# IOMOD-MCP23008-v1_0.net
KiCad netlist of a schematic drawn in EAGLE
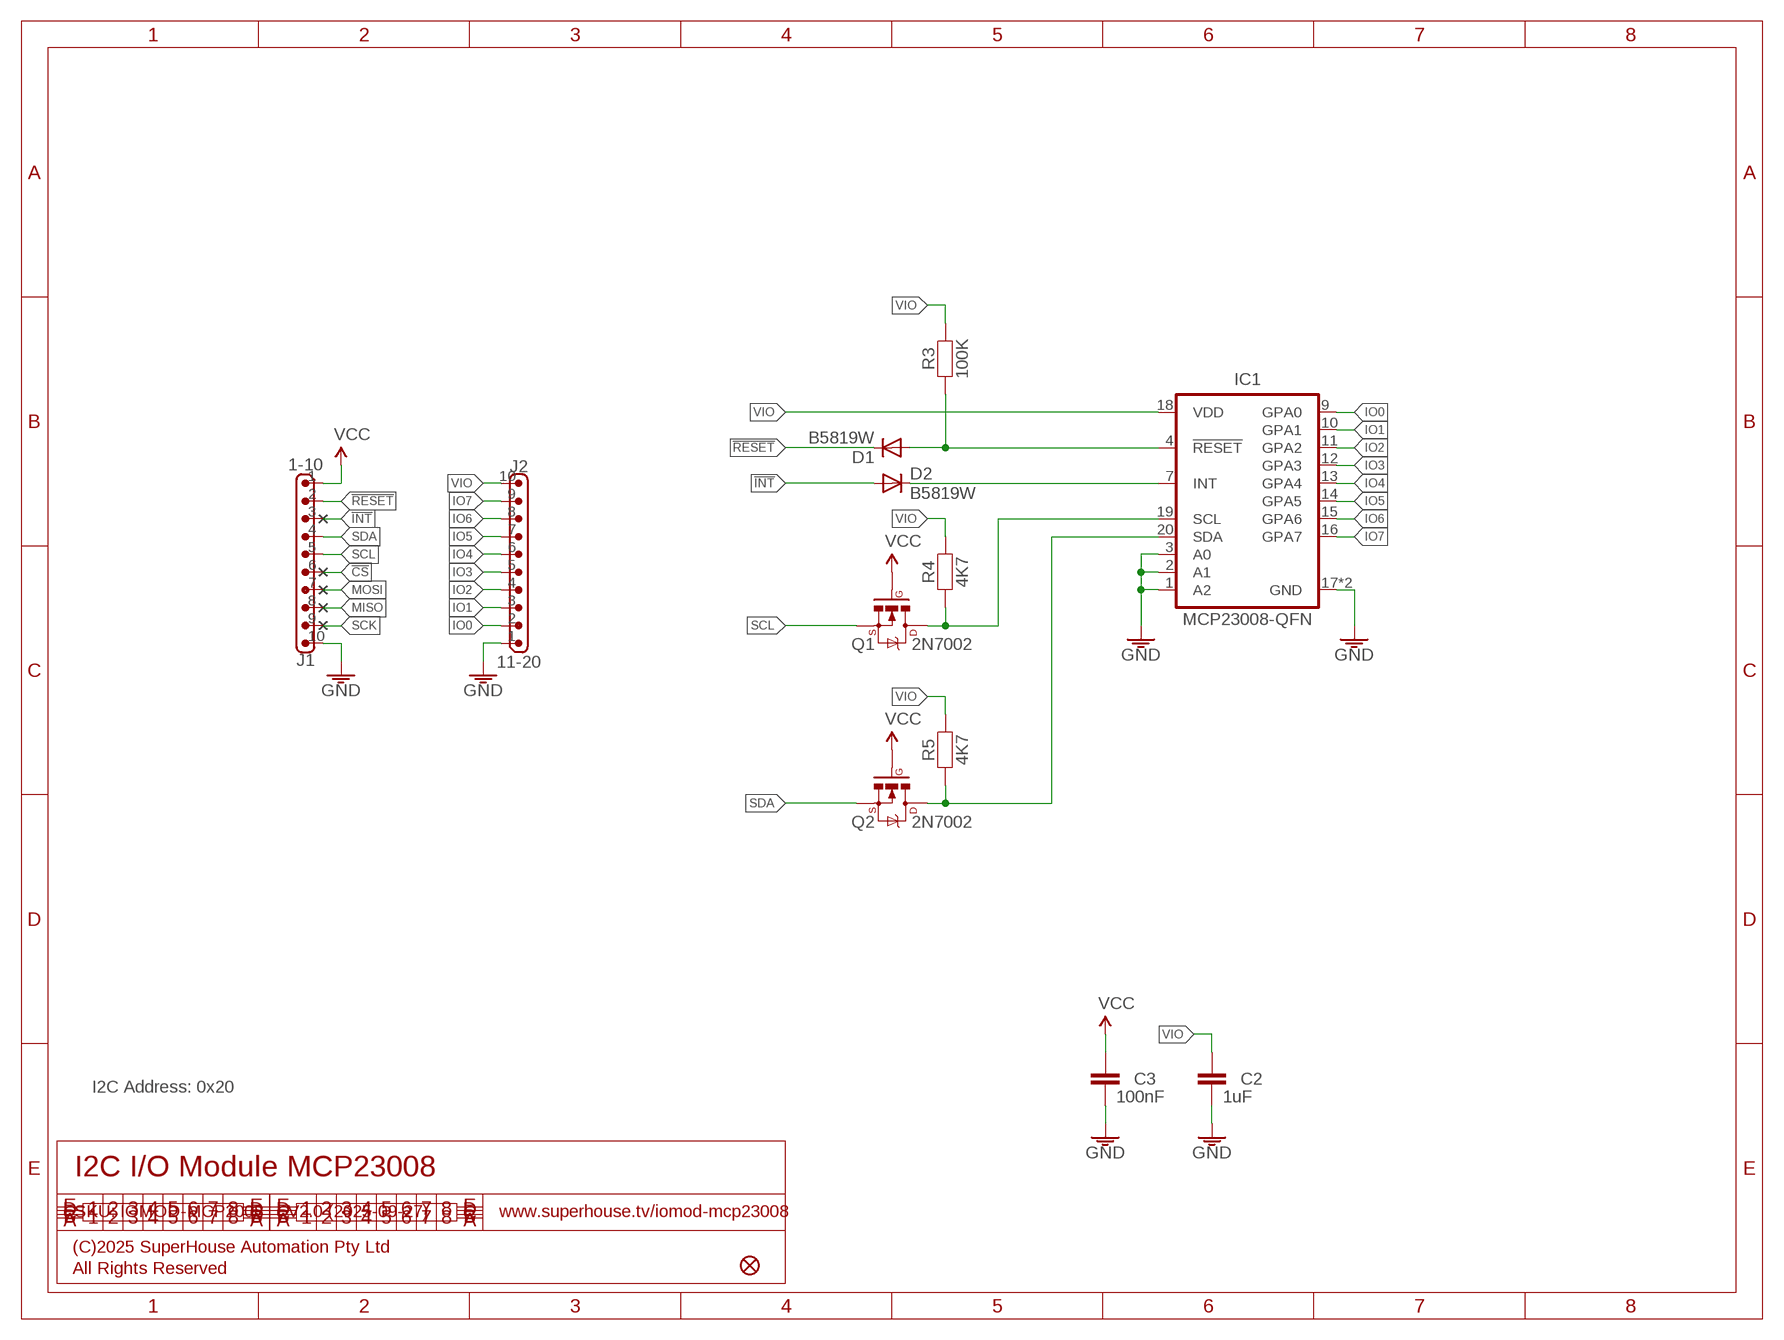
[diagram p0: schematic, sheet 1]

(export (version "E")
  (design (tool "Eeschema 10.0.6"))
  (components
    (comp (ref "C2")
      (value "1uF")
      (footprint "eagle-import:C0603")
      (libsource (lib "eagle-import") (part "CAP0603"))
    )
    (comp (ref "C3")
      (value "100nF")
      (footprint "eagle-import:C0603")
      (libsource (lib "eagle-import") (part "CAP0603"))
    )
    (comp (ref "D1")
      (value "B5819W")
      (footprint "eagle-import:SOD-123")
      (libsource (lib "eagle-import") (part "DIODE-SOD123"))
    )
    (comp (ref "D2")
      (value "B5819W")
      (footprint "eagle-import:SOD-123")
      (libsource (lib "eagle-import") (part "DIODE-SOD123"))
    )
    (comp (ref "FID1")
      (value "FIDUCIAL1X2")
      (footprint "eagle-import:FIDUCIAL-1X2")
      (libsource (lib "eagle-import") (part "FIDUCIAL1X2"))
    )
    (comp (ref "IC1")
      (value "MCP23008-QFN")
      (footprint "eagle-import:QFN-20")
      (libsource (lib "eagle-import") (part "MCP23008-QFN"))
    )
    (comp (ref "J1")
      (value "1-10")
      (footprint "eagle-import:1X10-2.00-P-ABOVE")
      (libsource (lib "eagle-import") (part "M10-2.00-P-ABOVE"))
    )
    (comp (ref "J2")
      (value "11-20")
      (footprint "eagle-import:1X10-2.00-P-ABOVE")
      (libsource (lib "eagle-import") (part "M10-2.00-P-ABOVE"))
    )
    (comp (ref "Q1")
      (value "2N7002")
      (footprint "eagle-import:SOT23-3")
      (libsource (lib "eagle-import") (part "MOSFET-NCHANNEL-233"))
    )
    (comp (ref "Q2")
      (value "2N7002")
      (footprint "eagle-import:SOT23-3")
      (libsource (lib "eagle-import") (part "MOSFET-NCHANNEL-233"))
    )
    (comp (ref "R3")
      (value "100K")
      (footprint "eagle-import:R0603")
      (libsource (lib "eagle-import") (part "RESISTOR0603"))
    )
    (comp (ref "R4")
      (value "4K7")
      (footprint "eagle-import:R0603")
      (libsource (lib "eagle-import") (part "RESISTOR0603"))
    )
    (comp (ref "R5")
      (value "4K7")
      (footprint "eagle-import:R0603")
      (libsource (lib "eagle-import") (part "RESISTOR0603"))
    )
  )
  (nets
    (net (code "1") (name "/~{CS}") (class "Default")
      (node (ref "J1") (pin "6") (pinfunction "6_6") (pintype "passive"))
    )
    (net (code "2") (name "/~{INT}") (class "Default")
      (node (ref "D2") (pin "2") (pinfunction "A_2") (pintype "passive"))
      (node (ref "J1") (pin "3") (pinfunction "3_3") (pintype "passive"))
    )
    (net (code "3") (name "/~{RESET}") (class "Default")
      (node (ref "D1") (pin "1") (pinfunction "C_1") (pintype "passive"))
      (node (ref "J1") (pin "2") (pinfunction "2_2") (pintype "passive"))
    )
    (net (code "4") (name "GND") (class "Default")
      (node (ref "C2") (pin "2") (pinfunction "2_2") (pintype "passive"))
      (node (ref "C3") (pin "2") (pinfunction "2_2") (pintype "passive"))
      (node (ref "IC1") (pin "1") (pinfunction "A2_1") (pintype "input"))
      (node (ref "IC1") (pin "17") (pinfunction "GND_17") (pintype "power_in"))
      (node (ref "IC1") (pin "2") (pinfunction "A1_2") (pintype "input"))
      (node (ref "IC1") (pin "3") (pinfunction "A0_3") (pintype "input"))
      (node (ref "IC1") (pin "TGND") (pinfunction "GND_TGND") (pintype "power_in"))
      (node (ref "J1") (pin "10") (pinfunction "10_10") (pintype "passive"))
      (node (ref "J2") (pin "1") (pinfunction "1_1") (pintype "passive"))
    )
    (net (code "5") (name "IO0") (class "Default")
      (node (ref "IC1") (pin "9") (pinfunction "GPA0_9") (pintype "bidirectional"))
      (node (ref "J2") (pin "2") (pinfunction "2_2") (pintype "passive"))
    )
    (net (code "6") (name "IO1") (class "Default")
      (node (ref "IC1") (pin "10") (pinfunction "GPA1_10") (pintype "bidirectional"))
      (node (ref "J2") (pin "3") (pinfunction "3_3") (pintype "passive"))
    )
    (net (code "7") (name "IO2") (class "Default")
      (node (ref "IC1") (pin "11") (pinfunction "GPA2_11") (pintype "bidirectional"))
      (node (ref "J2") (pin "4") (pinfunction "4_4") (pintype "passive"))
    )
    (net (code "8") (name "IO3") (class "Default")
      (node (ref "IC1") (pin "12") (pinfunction "GPA3_12") (pintype "bidirectional"))
      (node (ref "J2") (pin "5") (pinfunction "5_5") (pintype "passive"))
    )
    (net (code "9") (name "IO4") (class "Default")
      (node (ref "IC1") (pin "13") (pinfunction "GPA4_13") (pintype "bidirectional"))
      (node (ref "J2") (pin "6") (pinfunction "6_6") (pintype "passive"))
    )
    (net (code "10") (name "IO5") (class "Default")
      (node (ref "IC1") (pin "14") (pinfunction "GPA5_14") (pintype "bidirectional"))
      (node (ref "J2") (pin "7") (pinfunction "7_7") (pintype "passive"))
    )
    (net (code "11") (name "IO6") (class "Default")
      (node (ref "IC1") (pin "15") (pinfunction "GPA6_15") (pintype "bidirectional"))
      (node (ref "J2") (pin "8") (pinfunction "8_8") (pintype "passive"))
    )
    (net (code "12") (name "IO7") (class "Default")
      (node (ref "IC1") (pin "16") (pinfunction "GPA7_16") (pintype "bidirectional"))
      (node (ref "J2") (pin "9") (pinfunction "9_9") (pintype "passive"))
    )
    (net (code "13") (name "MISO") (class "Default")
      (node (ref "J1") (pin "8") (pinfunction "8_8") (pintype "passive"))
    )
    (net (code "14") (name "MOSI") (class "Default")
      (node (ref "J1") (pin "7") (pinfunction "7_7") (pintype "passive"))
    )
    (net (code "15") (name "Net-(D1-A)") (class "Default")
      (node (ref "D1") (pin "2") (pinfunction "A_2") (pintype "passive"))
      (node (ref "IC1") (pin "4") (pinfunction "~{RESET}_4") (pintype "input"))
      (node (ref "R3") (pin "1") (pinfunction "1_1") (pintype "passive"))
    )
    (net (code "16") (name "Net-(D2-C)") (class "Default")
      (node (ref "D2") (pin "1") (pinfunction "C_1") (pintype "passive"))
      (node (ref "IC1") (pin "7") (pinfunction "INT_7") (pintype "output"))
    )
    (net (code "17") (name "Net-(IC1-SCL)") (class "Default")
      (node (ref "IC1") (pin "19") (pinfunction "SCL_19") (pintype "input"))
      (node (ref "Q1") (pin "3") (pinfunction "D_3") (pintype "passive"))
      (node (ref "R4") (pin "1") (pinfunction "1_1") (pintype "passive"))
    )
    (net (code "18") (name "Net-(IC1-SDA)") (class "Default")
      (node (ref "IC1") (pin "20") (pinfunction "SDA_20") (pintype "bidirectional"))
      (node (ref "Q2") (pin "3") (pinfunction "D_3") (pintype "passive"))
      (node (ref "R5") (pin "1") (pinfunction "1_1") (pintype "passive"))
    )
    (net (code "19") (name "SCK") (class "Default")
      (node (ref "J1") (pin "9") (pinfunction "9_9") (pintype "passive"))
    )
    (net (code "20") (name "SCL") (class "Default")
      (node (ref "J1") (pin "5") (pinfunction "5_5") (pintype "passive"))
      (node (ref "Q1") (pin "2") (pinfunction "S_2") (pintype "passive"))
    )
    (net (code "21") (name "SDA") (class "Default")
      (node (ref "J1") (pin "4") (pinfunction "4_4") (pintype "passive"))
      (node (ref "Q2") (pin "2") (pinfunction "S_2") (pintype "passive"))
    )
    (net (code "22") (name "VCC") (class "Default")
      (node (ref "C3") (pin "1") (pinfunction "1_1") (pintype "passive"))
      (node (ref "J1") (pin "1") (pinfunction "1_1") (pintype "passive"))
      (node (ref "Q1") (pin "1") (pinfunction "G_1") (pintype "passive"))
      (node (ref "Q2") (pin "1") (pinfunction "G_1") (pintype "passive"))
    )
    (net (code "23") (name "VIO") (class "Default")
      (node (ref "C2") (pin "1") (pinfunction "1_1") (pintype "passive"))
      (node (ref "IC1") (pin "18") (pinfunction "VDD_18") (pintype "power_in"))
      (node (ref "J2") (pin "10") (pinfunction "10_10") (pintype "passive"))
      (node (ref "R3") (pin "2") (pinfunction "2_2") (pintype "passive"))
      (node (ref "R4") (pin "2") (pinfunction "2_2") (pintype "passive"))
      (node (ref "R5") (pin "2") (pinfunction "2_2") (pintype "passive"))
    )
  )
)
